# pico_test_synth1.net
KiCad netlist of a schematic drawn in EAGLE
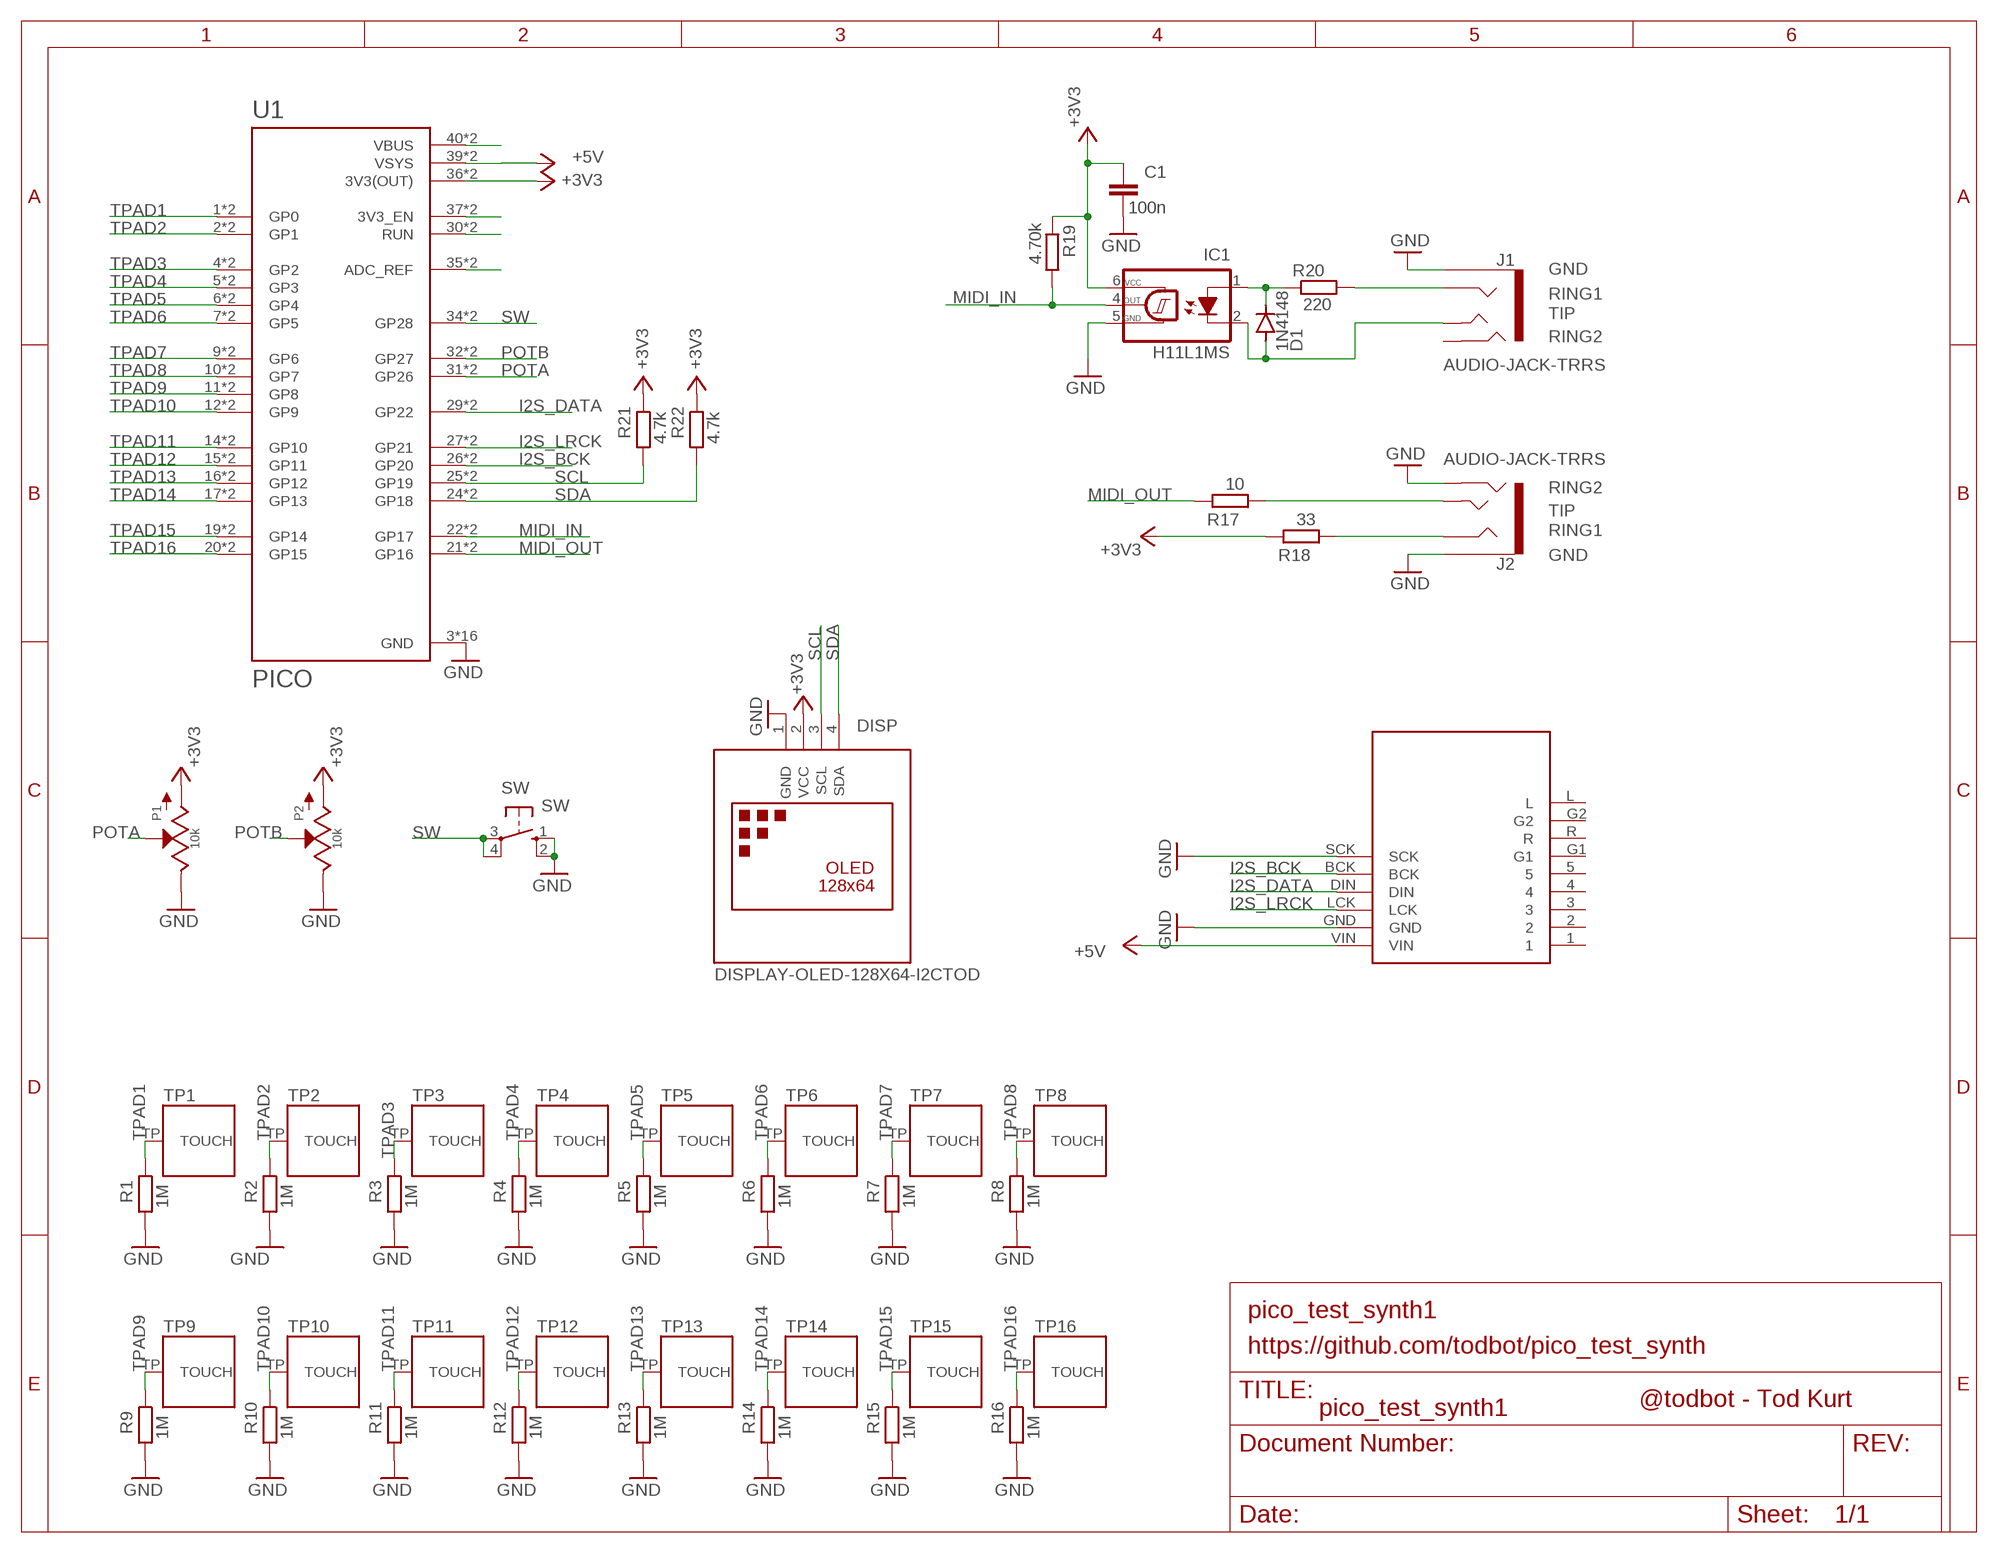
[diagram p0: schematic, sheet 1]

(export (version "E")
  (design (tool "Eeschema 10.0.6"))
  (components
    (comp (ref "C1")
      (value "100n")
      (footprint "eagle-import:C0805")
      (libsource (lib "eagle-import") (part "C-EUC0805"))
    )
    (comp (ref "D1")
      (value "1N4148")
      (footprint "eagle-import:SOD123")
      (libsource (lib "eagle-import") (part "DIODE-SOD123"))
    )
    (comp (ref "DISP")
      (value "DISPLAY-OLED-128X64-I2CTOD")
      (footprint "eagle-import:DISPLAY-OLED-128X64-I2C-TOD")
      (libsource (lib "eagle-import") (part "DISPLAY-OLED-128X64-I2CTOD"))
    )
    (comp (ref "IC1")
      (value "H11L1MS")
      (footprint "eagle-import:DIL6-SMD")
      (libsource (lib "eagle-import") (part "H11LMS1"))
    )
    (comp (ref "J1")
      (value "AUDIO-JACK-TRRS")
      (footprint "eagle-import:PJ-320D_SPARKFUN")
      (fields (field (name "MPN") "PJ-320D"))
      (libsource (lib "eagle-import") (part "AUDIO-JACK-TRRS"))
    )
    (comp (ref "J2")
      (value "AUDIO-JACK-TRRS")
      (footprint "eagle-import:PJ-320D_SPARKFUN")
      (fields (field (name "MPN") "PJ-320D") (field (name "LCSC") "C431535"))
      (libsource (lib "eagle-import") (part "AUDIO-JACK-TRRS"))
    )
    (comp (ref "P1")
      (value "10k")
      (footprint "eagle-import:OG-POTS_ALPS_POT_VERTICAL_WITHBIGKNOB")
      (libsource (lib "eagle-import") (part "POTZEPHPOT_BIGKNOB"))
    )
    (comp (ref "P2")
      (value "10k")
      (footprint "eagle-import:OG-POTS_ALPS_POT_VERTICAL_WITHBIGKNOB")
      (libsource (lib "eagle-import") (part "POTZEPHPOT_BIGKNOB"))
    )
    (comp (ref "R1")
      (value "1M")
      (footprint "eagle-import:R0805")
      (libsource (lib "eagle-import") (part "R-EU_R0805"))
    )
    (comp (ref "R2")
      (value "1M")
      (footprint "eagle-import:R0805")
      (libsource (lib "eagle-import") (part "R-EU_R0805"))
    )
    (comp (ref "R3")
      (value "1M")
      (footprint "eagle-import:R0805")
      (libsource (lib "eagle-import") (part "R-EU_R0805"))
    )
    (comp (ref "R4")
      (value "1M")
      (footprint "eagle-import:R0805")
      (libsource (lib "eagle-import") (part "R-EU_R0805"))
    )
    (comp (ref "R5")
      (value "1M")
      (footprint "eagle-import:R0805")
      (libsource (lib "eagle-import") (part "R-EU_R0805"))
    )
    (comp (ref "R6")
      (value "1M")
      (footprint "eagle-import:R0805")
      (libsource (lib "eagle-import") (part "R-EU_R0805"))
    )
    (comp (ref "R7")
      (value "1M")
      (footprint "eagle-import:R0805")
      (libsource (lib "eagle-import") (part "R-EU_R0805"))
    )
    (comp (ref "R8")
      (value "1M")
      (footprint "eagle-import:R0805")
      (libsource (lib "eagle-import") (part "R-EU_R0805"))
    )
    (comp (ref "R9")
      (value "1M")
      (footprint "eagle-import:R0805")
      (libsource (lib "eagle-import") (part "R-EU_R0805"))
    )
    (comp (ref "R10")
      (value "1M")
      (footprint "eagle-import:R0805")
      (libsource (lib "eagle-import") (part "R-EU_R0805"))
    )
    (comp (ref "R11")
      (value "1M")
      (footprint "eagle-import:R0805")
      (libsource (lib "eagle-import") (part "R-EU_R0805"))
    )
    (comp (ref "R12")
      (value "1M")
      (footprint "eagle-import:R0805")
      (libsource (lib "eagle-import") (part "R-EU_R0805"))
    )
    (comp (ref "R13")
      (value "1M")
      (footprint "eagle-import:R0805")
      (libsource (lib "eagle-import") (part "R-EU_R0805"))
    )
    (comp (ref "R14")
      (value "1M")
      (footprint "eagle-import:R0805")
      (libsource (lib "eagle-import") (part "R-EU_R0805"))
    )
    (comp (ref "R15")
      (value "1M")
      (footprint "eagle-import:R0805")
      (libsource (lib "eagle-import") (part "R-EU_R0805"))
    )
    (comp (ref "R16")
      (value "1M")
      (footprint "eagle-import:R0805")
      (libsource (lib "eagle-import") (part "R-EU_R0805"))
    )
    (comp (ref "R17")
      (value "10")
      (footprint "eagle-import:R0805")
      (libsource (lib "eagle-import") (part "R-EU_R0805"))
    )
    (comp (ref "R18")
      (value "33")
      (footprint "eagle-import:R0805")
      (libsource (lib "eagle-import") (part "R-EU_R0805"))
    )
    (comp (ref "R19")
      (value "4.70k")
      (footprint "eagle-import:R0805")
      (libsource (lib "eagle-import") (part "R-EU_R0805"))
    )
    (comp (ref "R20")
      (value "220")
      (footprint "eagle-import:R0805")
      (libsource (lib "eagle-import") (part "R-EU_R0805"))
    )
    (comp (ref "R21")
      (value "4.7k")
      (footprint "eagle-import:R0805")
      (libsource (lib "eagle-import") (part "R-EU_R0805"))
    )
    (comp (ref "R22")
      (value "4.7k")
      (footprint "eagle-import:R0805")
      (libsource (lib "eagle-import") (part "R-EU_R0805"))
    )
    (comp (ref "SW")
      (value "SW")
      (footprint "eagle-import:B3F-10XX")
      (fields (field (name "MPN") "B3F-1000"))
      (libsource (lib "eagle-import") (part "10-XX"))
    )
    (comp (ref "TP1")
      (value "TOUCHPADA")
      (footprint "eagle-import:TOUCHPADA_0.5IN")
      (libsource (lib "eagle-import") (part "TOUCHPADA"))
    )
    (comp (ref "TP2")
      (value "TOUCHPADA")
      (footprint "eagle-import:TOUCHPADA_0.5IN")
      (libsource (lib "eagle-import") (part "TOUCHPADA"))
    )
    (comp (ref "TP3")
      (value "TOUCHPADA")
      (footprint "eagle-import:TOUCHPADA_0.5IN")
      (libsource (lib "eagle-import") (part "TOUCHPADA"))
    )
    (comp (ref "TP4")
      (value "TOUCHPADA")
      (footprint "eagle-import:TOUCHPADA_0.5IN")
      (libsource (lib "eagle-import") (part "TOUCHPADA"))
    )
    (comp (ref "TP5")
      (value "TOUCHPADA")
      (footprint "eagle-import:TOUCHPADA_0.5IN")
      (libsource (lib "eagle-import") (part "TOUCHPADA"))
    )
    (comp (ref "TP6")
      (value "TOUCHPADA")
      (footprint "eagle-import:TOUCHPADA_0.5IN")
      (libsource (lib "eagle-import") (part "TOUCHPADA"))
    )
    (comp (ref "TP7")
      (value "TOUCHPADA")
      (footprint "eagle-import:TOUCHPADA_0.5IN")
      (libsource (lib "eagle-import") (part "TOUCHPADA"))
    )
    (comp (ref "TP8")
      (value "TOUCHPADA")
      (footprint "eagle-import:TOUCHPADA_0.5IN")
      (libsource (lib "eagle-import") (part "TOUCHPADA"))
    )
    (comp (ref "TP9")
      (value "TOUCHPADA")
      (footprint "eagle-import:TOUCHPADA_0.5IN")
      (libsource (lib "eagle-import") (part "TOUCHPADA"))
    )
    (comp (ref "TP10")
      (value "TOUCHPADA")
      (footprint "eagle-import:TOUCHPADA_0.5IN")
      (libsource (lib "eagle-import") (part "TOUCHPADA"))
    )
    (comp (ref "TP11")
      (value "TOUCHPADA")
      (footprint "eagle-import:TOUCHPADA_0.5IN")
      (libsource (lib "eagle-import") (part "TOUCHPADA"))
    )
    (comp (ref "TP12")
      (value "TOUCHPADA")
      (footprint "eagle-import:TOUCHPADA_0.5IN")
      (libsource (lib "eagle-import") (part "TOUCHPADA"))
    )
    (comp (ref "TP13")
      (value "TOUCHPADA")
      (footprint "eagle-import:TOUCHPADA_0.5IN")
      (libsource (lib "eagle-import") (part "TOUCHPADA"))
    )
    (comp (ref "TP14")
      (value "TOUCHPADA")
      (footprint "eagle-import:TOUCHPADA_0.5IN")
      (libsource (lib "eagle-import") (part "TOUCHPADA"))
    )
    (comp (ref "TP15")
      (value "TOUCHPADA")
      (footprint "eagle-import:TOUCHPADA_0.5IN")
      (libsource (lib "eagle-import") (part "TOUCHPADA"))
    )
    (comp (ref "TP16")
      (value "TOUCHPADA")
      (footprint "eagle-import:TOUCHPADA_0.5IN")
      (libsource (lib "eagle-import") (part "TOUCHPADA"))
    )
    (comp (ref "U1")
      (value "PICO")
      (footprint "eagle-import:PICO-PKG-NO_DEBUG")
      (libsource (lib "eagle-import") (part "RASPBERRY_PICO-NO_DEBUG"))
    )
    (comp (ref "U2")
      (value "I2S_PCM_51XX_SOUNDCARD")
      (footprint "eagle-import:I2S_PCM_5100_SOUNDCARD")
      (libsource (lib "eagle-import") (part "I2S_PCM_51XX_SOUNDCARD"))
    )
  )
  (nets
    (net (code "1") (name "+3V3") (class "Default")
      (node (ref "C1") (pin "1") (pinfunction "1_1") (pintype "passive"))
      (node (ref "DISP") (pin "2") (pinfunction "VCC_2") (pintype "power_in"))
      (node (ref "IC1") (pin "6") (pinfunction "VCC_6") (pintype "power_in"))
      (node (ref "P1") (pin "P$3") (pinfunction "A_P$3") (pintype "passive"))
      (node (ref "P2") (pin "P$3") (pinfunction "A_P$3") (pintype "passive"))
      (node (ref "R18") (pin "1") (pinfunction "1_1") (pintype "passive"))
      (node (ref "R19") (pin "1") (pinfunction "1_1") (pintype "passive"))
      (node (ref "R21") (pin "1") (pinfunction "1_1") (pintype "passive"))
      (node (ref "R22") (pin "1") (pinfunction "1_1") (pintype "passive"))
      (node (ref "U1") (pin "36") (pinfunction "3V3(OUT)_36") (pintype "power_in"))
      (node (ref "U1") (pin "P$36") (pinfunction "3V3(OUT)_P$36") (pintype "power_in"))
    )
    (net (code "2") (name "+5V") (class "Default")
      (node (ref "U1") (pin "39") (pinfunction "VSYS_39") (pintype "power_in"))
      (node (ref "U1") (pin "P$39") (pinfunction "VSYS_P$39") (pintype "power_in"))
      (node (ref "U2") (pin "VIN") (pinfunction "VIN_VIN") (pintype "bidirectional"))
    )
    (net (code "3") (name "/I2S_BCK") (class "Default")
      (node (ref "U1") (pin "26") (pinfunction "GP20_26") (pintype "bidirectional"))
      (node (ref "U1") (pin "P$26") (pinfunction "GP20_P$26") (pintype "bidirectional"))
      (node (ref "U2") (pin "BCK") (pinfunction "BCK_BCK") (pintype "bidirectional"))
    )
    (net (code "4") (name "/I2S_DATA") (class "Default")
      (node (ref "U1") (pin "29") (pinfunction "GP22_29") (pintype "bidirectional"))
      (node (ref "U1") (pin "P$29") (pinfunction "GP22_P$29") (pintype "bidirectional"))
      (node (ref "U2") (pin "DIN") (pinfunction "DIN_DIN") (pintype "bidirectional"))
    )
    (net (code "5") (name "/I2S_LRCK") (class "Default")
      (node (ref "U1") (pin "27") (pinfunction "GP21_27") (pintype "bidirectional"))
      (node (ref "U1") (pin "P$27") (pinfunction "GP21_P$27") (pintype "bidirectional"))
      (node (ref "U2") (pin "LCK") (pinfunction "LCK_LCK") (pintype "bidirectional"))
    )
    (net (code "6") (name "/MIDI_IN") (class "Default")
      (node (ref "IC1") (pin "4") (pinfunction "OUT_4") (pintype "output"))
      (node (ref "R19") (pin "2") (pinfunction "2_2") (pintype "passive"))
      (node (ref "U1") (pin "22") (pinfunction "GP17_22") (pintype "bidirectional"))
      (node (ref "U1") (pin "P$22") (pinfunction "GP17_P$22") (pintype "bidirectional"))
    )
    (net (code "7") (name "/MIDI_OUT") (class "Default")
      (node (ref "R17") (pin "1") (pinfunction "1_1") (pintype "passive"))
      (node (ref "U1") (pin "21") (pinfunction "GP16_21") (pintype "bidirectional"))
      (node (ref "U1") (pin "P$21") (pinfunction "GP16_P$21") (pintype "bidirectional"))
    )
    (net (code "8") (name "/POTA") (class "Default")
      (node (ref "P1") (pin "P$2") (pinfunction "S_P$2") (pintype "passive"))
      (node (ref "U1") (pin "31") (pinfunction "GP26_31") (pintype "bidirectional"))
      (node (ref "U1") (pin "P$31") (pinfunction "GP26_P$31") (pintype "bidirectional"))
    )
    (net (code "9") (name "/POTB") (class "Default")
      (node (ref "P2") (pin "P$2") (pinfunction "S_P$2") (pintype "passive"))
      (node (ref "U1") (pin "32") (pinfunction "GP27_32") (pintype "bidirectional"))
      (node (ref "U1") (pin "P$32") (pinfunction "GP27_P$32") (pintype "bidirectional"))
    )
    (net (code "10") (name "/SCL") (class "Default")
      (node (ref "DISP") (pin "3") (pinfunction "SCL_3") (pintype "bidirectional"))
      (node (ref "R21") (pin "2") (pinfunction "2_2") (pintype "passive"))
      (node (ref "U1") (pin "25") (pinfunction "GP19_25") (pintype "bidirectional"))
      (node (ref "U1") (pin "P$25") (pinfunction "GP19_P$25") (pintype "bidirectional"))
    )
    (net (code "11") (name "/SDA") (class "Default")
      (node (ref "DISP") (pin "4") (pinfunction "SDA_4") (pintype "bidirectional"))
      (node (ref "R22") (pin "2") (pinfunction "2_2") (pintype "passive"))
      (node (ref "U1") (pin "24") (pinfunction "GP18_24") (pintype "bidirectional"))
      (node (ref "U1") (pin "P$24") (pinfunction "GP18_P$24") (pintype "bidirectional"))
    )
    (net (code "12") (name "/SW") (class "Default")
      (node (ref "SW") (pin "3") (pinfunction "P_3") (pintype "passive"))
      (node (ref "SW") (pin "4") (pinfunction "P1_4") (pintype "passive"))
      (node (ref "U1") (pin "34") (pinfunction "GP28_34") (pintype "bidirectional"))
      (node (ref "U1") (pin "P$34") (pinfunction "GP28_P$34") (pintype "bidirectional"))
    )
    (net (code "13") (name "/TPAD1") (class "Default")
      (node (ref "R1") (pin "1") (pinfunction "1_1") (pintype "passive"))
      (node (ref "TP1") (pin "TP") (pinfunction "TOUCH_TP") (pintype "bidirectional"))
      (node (ref "U1") (pin "1") (pinfunction "GP0_1") (pintype "bidirectional"))
      (node (ref "U1") (pin "P$1") (pinfunction "GP0_P$1") (pintype "bidirectional"))
    )
    (net (code "14") (name "/TPAD2") (class "Default")
      (node (ref "R2") (pin "1") (pinfunction "1_1") (pintype "passive"))
      (node (ref "TP2") (pin "TP") (pinfunction "TOUCH_TP") (pintype "bidirectional"))
      (node (ref "U1") (pin "2") (pinfunction "GP1_2") (pintype "bidirectional"))
      (node (ref "U1") (pin "P$2") (pinfunction "GP1_P$2") (pintype "bidirectional"))
    )
    (net (code "15") (name "/TPAD3") (class "Default")
      (node (ref "R3") (pin "1") (pinfunction "1_1") (pintype "passive"))
      (node (ref "TP3") (pin "TP") (pinfunction "TOUCH_TP") (pintype "bidirectional"))
      (node (ref "U1") (pin "4") (pinfunction "GP2_4") (pintype "bidirectional"))
      (node (ref "U1") (pin "P$4") (pinfunction "GP2_P$4") (pintype "bidirectional"))
    )
    (net (code "16") (name "/TPAD4") (class "Default")
      (node (ref "R4") (pin "1") (pinfunction "1_1") (pintype "passive"))
      (node (ref "TP4") (pin "TP") (pinfunction "TOUCH_TP") (pintype "bidirectional"))
      (node (ref "U1") (pin "5") (pinfunction "GP3_5") (pintype "bidirectional"))
      (node (ref "U1") (pin "P$5") (pinfunction "GP3_P$5") (pintype "bidirectional"))
    )
    (net (code "17") (name "/TPAD5") (class "Default")
      (node (ref "R5") (pin "1") (pinfunction "1_1") (pintype "passive"))
      (node (ref "TP5") (pin "TP") (pinfunction "TOUCH_TP") (pintype "bidirectional"))
      (node (ref "U1") (pin "6") (pinfunction "GP4_6") (pintype "bidirectional"))
      (node (ref "U1") (pin "P$6") (pinfunction "GP4_P$6") (pintype "bidirectional"))
    )
    (net (code "18") (name "/TPAD6") (class "Default")
      (node (ref "R6") (pin "1") (pinfunction "1_1") (pintype "passive"))
      (node (ref "TP6") (pin "TP") (pinfunction "TOUCH_TP") (pintype "bidirectional"))
      (node (ref "U1") (pin "7") (pinfunction "GP5_7") (pintype "bidirectional"))
      (node (ref "U1") (pin "P$7") (pinfunction "GP5_P$7") (pintype "bidirectional"))
    )
    (net (code "19") (name "/TPAD7") (class "Default")
      (node (ref "R7") (pin "1") (pinfunction "1_1") (pintype "passive"))
      (node (ref "TP7") (pin "TP") (pinfunction "TOUCH_TP") (pintype "bidirectional"))
      (node (ref "U1") (pin "9") (pinfunction "GP6_9") (pintype "bidirectional"))
      (node (ref "U1") (pin "P$9") (pinfunction "GP6_P$9") (pintype "bidirectional"))
    )
    (net (code "20") (name "/TPAD8") (class "Default")
      (node (ref "R8") (pin "1") (pinfunction "1_1") (pintype "passive"))
      (node (ref "TP8") (pin "TP") (pinfunction "TOUCH_TP") (pintype "bidirectional"))
      (node (ref "U1") (pin "10") (pinfunction "GP7_10") (pintype "bidirectional"))
      (node (ref "U1") (pin "P$10") (pinfunction "GP7_P$10") (pintype "bidirectional"))
    )
    (net (code "21") (name "/TPAD9") (class "Default")
      (node (ref "R9") (pin "1") (pinfunction "1_1") (pintype "passive"))
      (node (ref "TP9") (pin "TP") (pinfunction "TOUCH_TP") (pintype "bidirectional"))
      (node (ref "U1") (pin "11") (pinfunction "GP8_11") (pintype "bidirectional"))
      (node (ref "U1") (pin "P$11") (pinfunction "GP8_P$11") (pintype "bidirectional"))
    )
    (net (code "22") (name "/TPAD10") (class "Default")
      (node (ref "R10") (pin "1") (pinfunction "1_1") (pintype "passive"))
      (node (ref "TP10") (pin "TP") (pinfunction "TOUCH_TP") (pintype "bidirectional"))
      (node (ref "U1") (pin "12") (pinfunction "GP9_12") (pintype "bidirectional"))
      (node (ref "U1") (pin "P$12") (pinfunction "GP9_P$12") (pintype "bidirectional"))
    )
    (net (code "23") (name "/TPAD11") (class "Default")
      (node (ref "R11") (pin "1") (pinfunction "1_1") (pintype "passive"))
      (node (ref "TP11") (pin "TP") (pinfunction "TOUCH_TP") (pintype "bidirectional"))
      (node (ref "U1") (pin "14") (pinfunction "GP10_14") (pintype "bidirectional"))
      (node (ref "U1") (pin "P$14") (pinfunction "GP10_P$14") (pintype "bidirectional"))
    )
    (net (code "24") (name "/TPAD12") (class "Default")
      (node (ref "R12") (pin "1") (pinfunction "1_1") (pintype "passive"))
      (node (ref "TP12") (pin "TP") (pinfunction "TOUCH_TP") (pintype "bidirectional"))
      (node (ref "U1") (pin "15") (pinfunction "GP11_15") (pintype "bidirectional"))
      (node (ref "U1") (pin "P$15") (pinfunction "GP11_P$15") (pintype "bidirectional"))
    )
    (net (code "25") (name "/TPAD13") (class "Default")
      (node (ref "R13") (pin "1") (pinfunction "1_1") (pintype "passive"))
      (node (ref "TP13") (pin "TP") (pinfunction "TOUCH_TP") (pintype "bidirectional"))
      (node (ref "U1") (pin "16") (pinfunction "GP12_16") (pintype "bidirectional"))
      (node (ref "U1") (pin "P$16") (pinfunction "GP12_P$16") (pintype "bidirectional"))
    )
    (net (code "26") (name "/TPAD14") (class "Default")
      (node (ref "R14") (pin "1") (pinfunction "1_1") (pintype "passive"))
      (node (ref "TP14") (pin "TP") (pinfunction "TOUCH_TP") (pintype "bidirectional"))
      (node (ref "U1") (pin "17") (pinfunction "GP13_17") (pintype "bidirectional"))
      (node (ref "U1") (pin "P$17") (pinfunction "GP13_P$17") (pintype "bidirectional"))
    )
    (net (code "27") (name "/TPAD15") (class "Default")
      (node (ref "R15") (pin "1") (pinfunction "1_1") (pintype "passive"))
      (node (ref "TP15") (pin "TP") (pinfunction "TOUCH_TP") (pintype "bidirectional"))
      (node (ref "U1") (pin "19") (pinfunction "GP14_19") (pintype "bidirectional"))
      (node (ref "U1") (pin "P$19") (pinfunction "GP14_P$19") (pintype "bidirectional"))
    )
    (net (code "28") (name "/TPAD16") (class "Default")
      (node (ref "R16") (pin "1") (pinfunction "1_1") (pintype "passive"))
      (node (ref "TP16") (pin "TP") (pinfunction "TOUCH_TP") (pintype "bidirectional"))
      (node (ref "U1") (pin "20") (pinfunction "GP15_20") (pintype "bidirectional"))
      (node (ref "U1") (pin "P$20") (pinfunction "GP15_P$20") (pintype "bidirectional"))
    )
    (net (code "29") (name "GND") (class "Default")
      (node (ref "C1") (pin "2") (pinfunction "2_2") (pintype "passive"))
      (node (ref "DISP") (pin "1") (pinfunction "GND_1") (pintype "power_in"))
      (node (ref "IC1") (pin "5") (pinfunction "GND_5") (pintype "power_in"))
      (node (ref "J1") (pin "EARTH") (pinfunction "EARTH_EARTH") (pintype "bidirectional"))
      (node (ref "J2") (pin "EARTH") (pinfunction "EARTH_EARTH") (pintype "bidirectional"))
      (node (ref "J2") (pin "RING2") (pinfunction "RING2_RING2") (pintype "bidirectional"))
      (node (ref "P1") (pin "P$1") (pinfunction "E_P$1") (pintype "passive"))
      (node (ref "P2") (pin "P$1") (pinfunction "E_P$1") (pintype "passive"))
      (node (ref "R1") (pin "2") (pinfunction "2_2") (pintype "passive"))
      (node (ref "R10") (pin "2") (pinfunction "2_2") (pintype "passive"))
      (node (ref "R11") (pin "2") (pinfunction "2_2") (pintype "passive"))
      (node (ref "R12") (pin "2") (pinfunction "2_2") (pintype "passive"))
      (node (ref "R13") (pin "2") (pinfunction "2_2") (pintype "passive"))
      (node (ref "R14") (pin "2") (pinfunction "2_2") (pintype "passive"))
      (node (ref "R15") (pin "2") (pinfunction "2_2") (pintype "passive"))
      (node (ref "R16") (pin "2") (pinfunction "2_2") (pintype "passive"))
      (node (ref "R2") (pin "2") (pinfunction "2_2") (pintype "passive"))
      (node (ref "R3") (pin "2") (pinfunction "2_2") (pintype "passive"))
      (node (ref "R4") (pin "2") (pinfunction "2_2") (pintype "passive"))
      (node (ref "R5") (pin "2") (pinfunction "2_2") (pintype "passive"))
      (node (ref "R6") (pin "2") (pinfunction "2_2") (pintype "passive"))
      (node (ref "R7") (pin "2") (pinfunction "2_2") (pintype "passive"))
      (node (ref "R8") (pin "2") (pinfunction "2_2") (pintype "passive"))
      (node (ref "R9") (pin "2") (pinfunction "2_2") (pintype "passive"))
      (node (ref "SW") (pin "1") (pinfunction "S_1") (pintype "passive"))
      (node (ref "SW") (pin "2") (pinfunction "S1_2") (pintype "passive"))
      (node (ref "U1") (pin "13") (pinfunction "GND_13") (pintype "power_in"))
      (node (ref "U1") (pin "18") (pinfunction "GND_18") (pintype "power_in"))
      (node (ref "U1") (pin "23") (pinfunction "GND_23") (pintype "power_in"))
      (node (ref "U1") (pin "28") (pinfunction "GND_28") (pintype "power_in"))
      (node (ref "U1") (pin "3") (pinfunction "GND_3") (pintype "power_in"))
      (node (ref "U1") (pin "33") (pinfunction "GND_33") (pintype "power_in"))
      (node (ref "U1") (pin "38") (pinfunction "GND_38") (pintype "power_in"))
      (node (ref "U1") (pin "8") (pinfunction "GND_8") (pintype "power_in"))
      (node (ref "U1") (pin "P$13") (pinfunction "GND_P$13") (pintype "power_in"))
      (node (ref "U1") (pin "P$18") (pinfunction "GND_P$18") (pintype "power_in"))
      (node (ref "U1") (pin "P$23") (pinfunction "GND_P$23") (pintype "power_in"))
      (node (ref "U1") (pin "P$28") (pinfunction "GND_P$28") (pintype "power_in"))
      (node (ref "U1") (pin "P$3") (pinfunction "GND_P$3") (pintype "power_in"))
      (node (ref "U1") (pin "P$33") (pinfunction "GND_P$33") (pintype "power_in"))
      (node (ref "U1") (pin "P$38") (pinfunction "GND_P$38") (pintype "power_in"))
      (node (ref "U1") (pin "P$8") (pinfunction "GND_P$8") (pintype "power_in"))
      (node (ref "U2") (pin "GND") (pinfunction "GND_GND") (pintype "bidirectional"))
      (node (ref "U2") (pin "SCK") (pinfunction "SCK_SCK") (pintype "bidirectional"))
    )
    (net (code "30") (name "Net-(IC1-A)") (class "Default")
      (node (ref "D1") (pin "C") (pinfunction "C_C") (pintype "passive"))
      (node (ref "IC1") (pin "1") (pinfunction "A_1") (pintype "passive"))
      (node (ref "R20") (pin "1") (pinfunction "1_1") (pintype "passive"))
    )
    (net (code "31") (name "Net-(IC1-C)") (class "Default")
      (node (ref "D1") (pin "A") (pinfunction "A_A") (pintype "passive"))
      (node (ref "IC1") (pin "2") (pinfunction "C_2") (pintype "passive"))
      (node (ref "J1") (pin "TIP") (pinfunction "TIP_TIP") (pintype "bidirectional"))
    )
    (net (code "32") (name "Net-(J1-PadRING1)") (class "Default")
      (node (ref "J1") (pin "RING1") (pinfunction "RING1_RING1") (pintype "bidirectional"))
      (node (ref "R20") (pin "2") (pinfunction "2_2") (pintype "passive"))
    )
    (net (code "33") (name "Net-(J2-PadRING1)") (class "Default")
      (node (ref "J2") (pin "RING1") (pinfunction "RING1_RING1") (pintype "bidirectional"))
      (node (ref "R18") (pin "2") (pinfunction "2_2") (pintype "passive"))
    )
    (net (code "34") (name "Net-(J2-PadTIP)") (class "Default")
      (node (ref "J2") (pin "TIP") (pinfunction "TIP_TIP") (pintype "bidirectional"))
      (node (ref "R17") (pin "2") (pinfunction "2_2") (pintype "passive"))
    )
    (net (code "35") (name "Net-(U1-3V3_EN-Pad37)") (class "Default")
      (node (ref "U1") (pin "37") (pinfunction "3V3_EN_37") (pintype "input"))
      (node (ref "U1") (pin "P$37") (pinfunction "3V3_EN_P$37") (pintype "input"))
    )
    (net (code "36") (name "Net-(U1-ADC_REF-Pad35)") (class "Default")
      (node (ref "U1") (pin "35") (pinfunction "ADC_REF_35") (pintype "input"))
      (node (ref "U1") (pin "P$35") (pinfunction "ADC_REF_P$35") (pintype "input"))
    )
    (net (code "37") (name "Net-(U1-RUN-Pad30)") (class "Default")
      (node (ref "U1") (pin "30") (pinfunction "RUN_30") (pintype "input"))
      (node (ref "U1") (pin "P$30") (pinfunction "RUN_P$30") (pintype "input"))
    )
    (net (code "38") (name "Net-(U1-VBUS-Pad40)") (class "Default")
      (node (ref "U1") (pin "40") (pinfunction "VBUS_40") (pintype "power_in"))
      (node (ref "U1") (pin "P$40") (pinfunction "VBUS_P$40") (pintype "power_in"))
    )
    (net (code "39") (name "unconnected-(J1-PadRING2)") (class "Default")
      (node (ref "J1") (pin "RING2") (pinfunction "RING2_RING2") (pintype "bidirectional"))
    )
    (net (code "40") (name "unconnected-(U2-Pad1)") (class "Default")
      (node (ref "U2") (pin "1") (pinfunction "1_1") (pintype "bidirectional"))
    )
    (net (code "41") (name "unconnected-(U2-Pad2)") (class "Default")
      (node (ref "U2") (pin "2") (pinfunction "2_2") (pintype "bidirectional"))
    )
    (net (code "42") (name "unconnected-(U2-Pad3)") (class "Default")
      (node (ref "U2") (pin "3") (pinfunction "3_3") (pintype "bidirectional"))
    )
    (net (code "43") (name "unconnected-(U2-Pad4)") (class "Default")
      (node (ref "U2") (pin "4") (pinfunction "4_4") (pintype "bidirectional"))
    )
    (net (code "44") (name "unconnected-(U2-Pad5)") (class "Default")
      (node (ref "U2") (pin "5") (pinfunction "5_5") (pintype "bidirectional"))
    )
    (net (code "45") (name "unconnected-(U2-PadG1)") (class "Default")
      (node (ref "U2") (pin "G1") (pinfunction "G1_G1") (pintype "bidirectional"))
    )
    (net (code "46") (name "unconnected-(U2-PadG2)") (class "Default")
      (node (ref "U2") (pin "G2") (pinfunction "G2_G2") (pintype "bidirectional"))
    )
    (net (code "47") (name "unconnected-(U2-PadL)") (class "Default")
      (node (ref "U2") (pin "L") (pinfunction "L_L") (pintype "bidirectional"))
    )
    (net (code "48") (name "unconnected-(U2-PadR)") (class "Default")
      (node (ref "U2") (pin "R") (pinfunction "R_R") (pintype "bidirectional"))
    )
  )
)
